# FPGA_PWR_CONFIG.net
KiCad netlist of a schematic drawn in Altium Designer
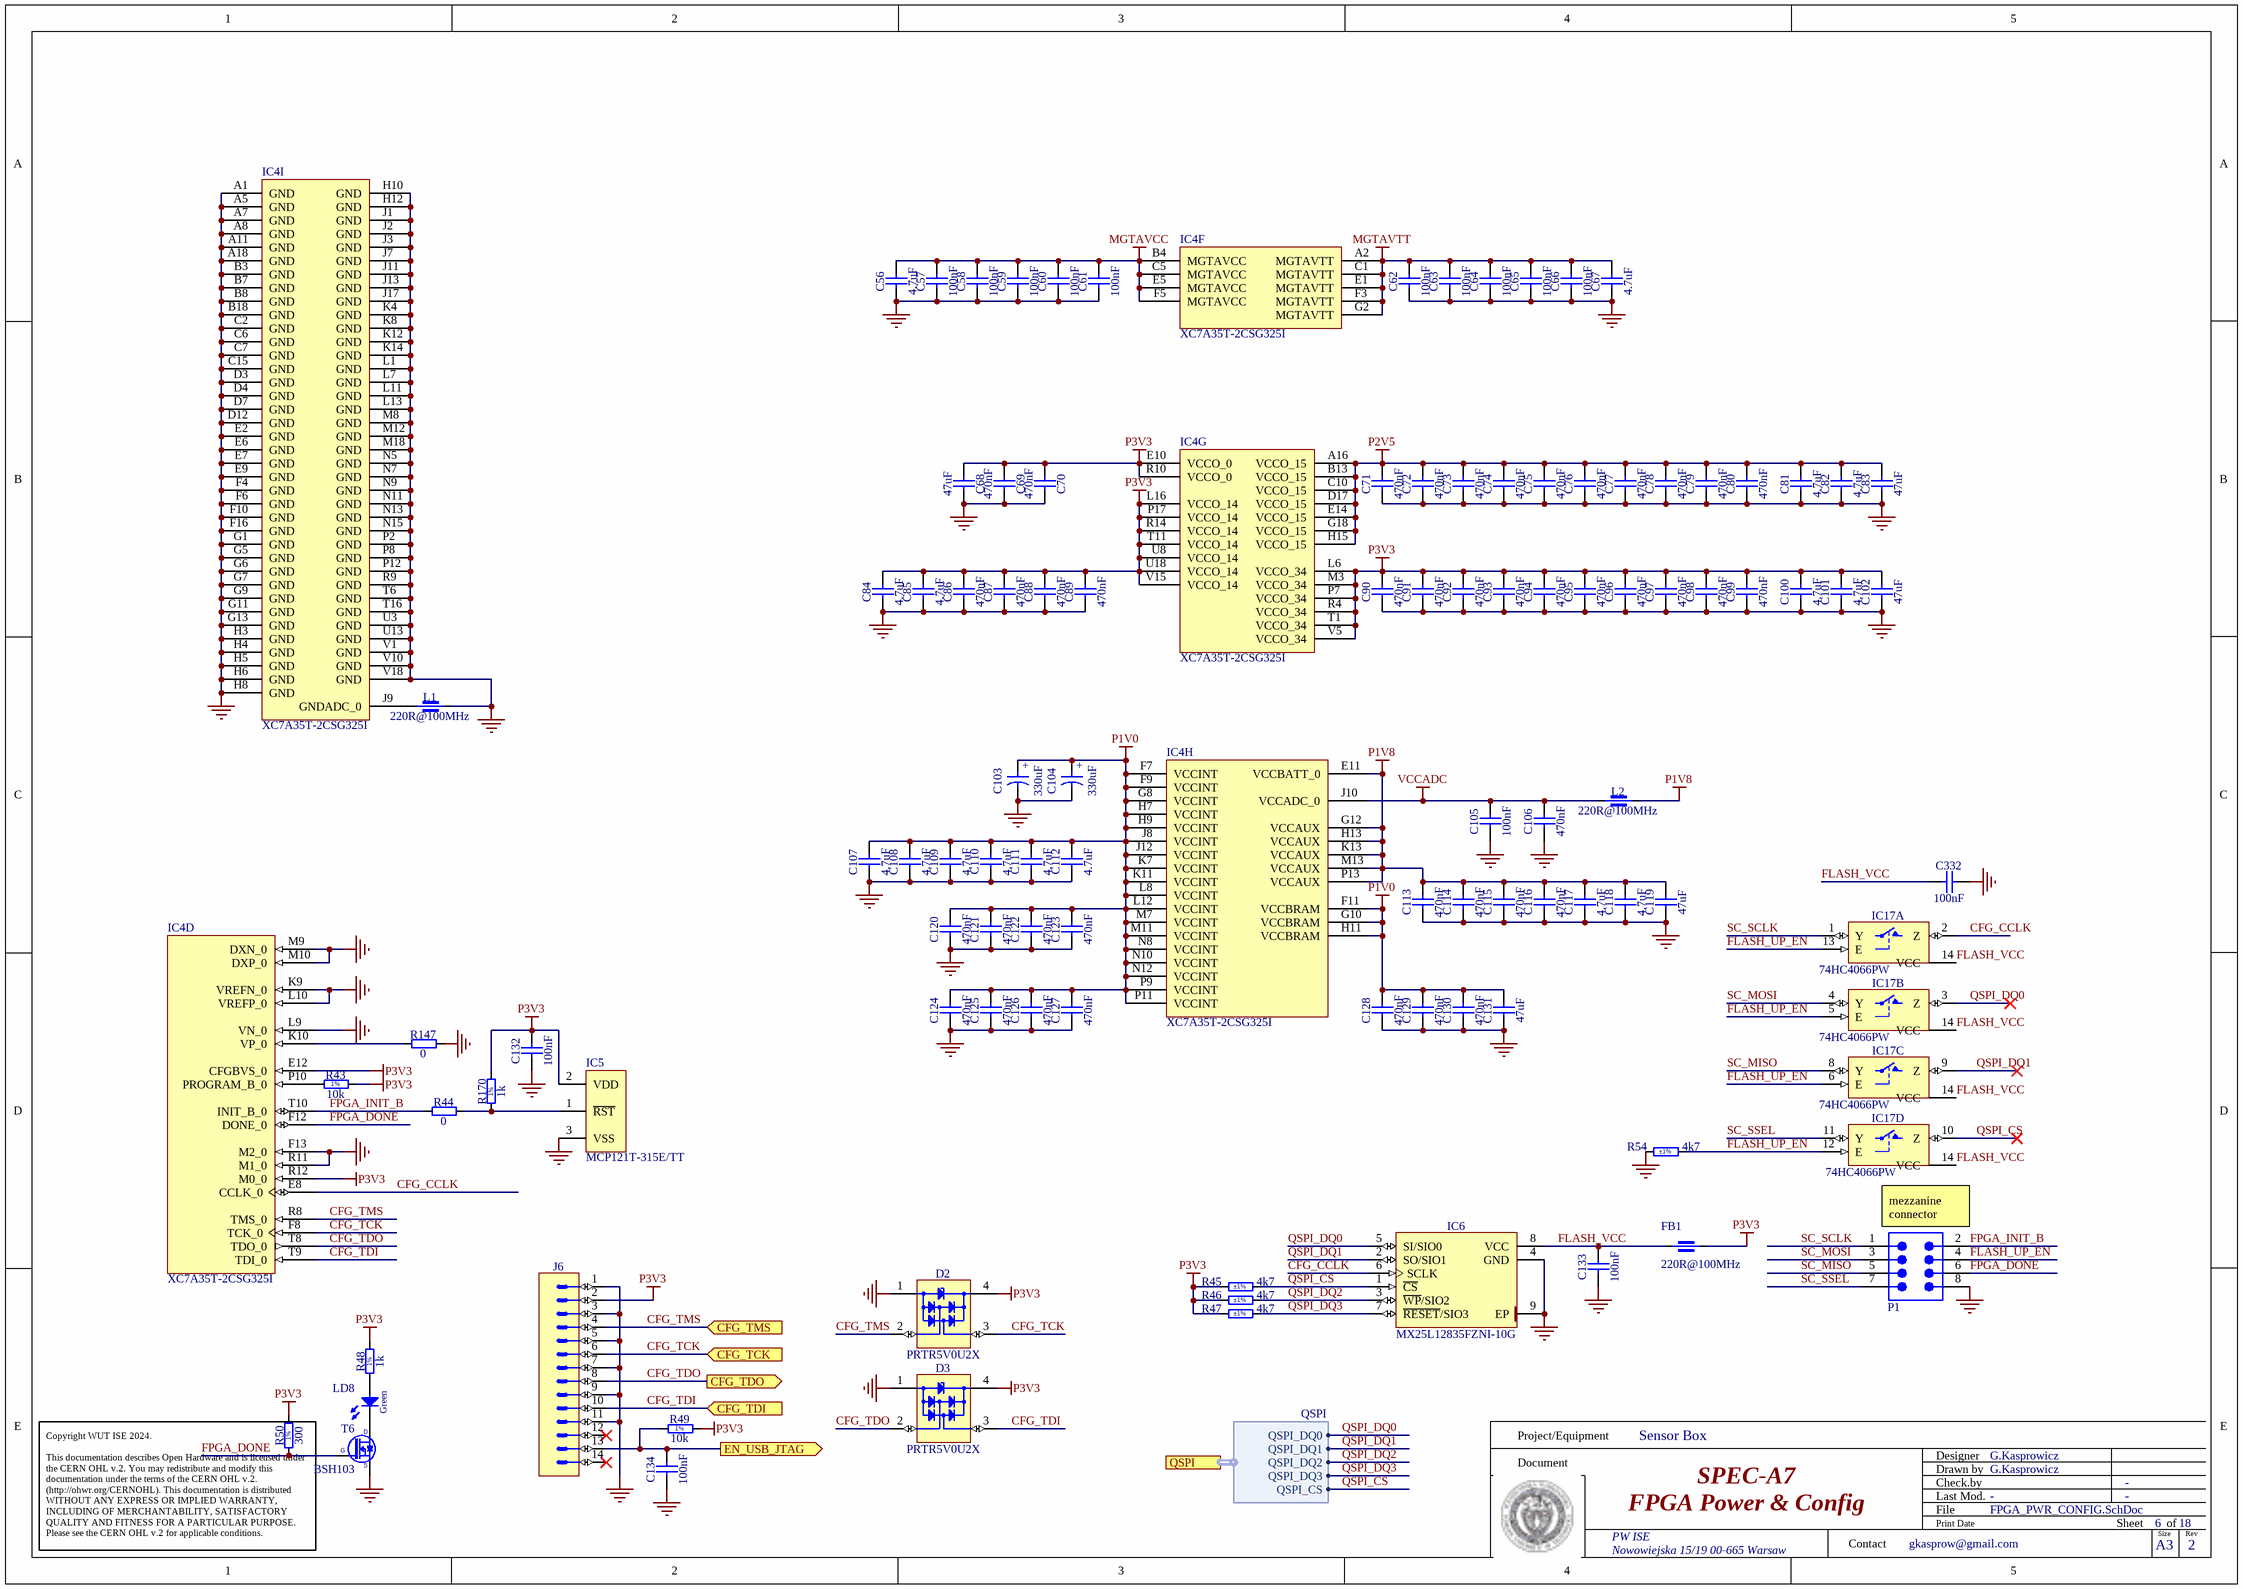
[diagram p0: FPGA_PWR_CONFIG.SchDoc]

(export (version "E")
  (design (tool "Eeschema 10.0.6"))
  (components
    (comp (ref "C56")
      (value "4.7uF")
      (footprint "CAPC1005X55N")
      (description "Non-polarised capacitor")
      (fields
        (field (name "PART NUMBER") "CC0402_4.7UF_6.3V_20%_X5R")
        (field (name "VOLTAGE") "6.3V")
        (field (name "AUTHOR") "CERN DEM JLC")
      )
      (libsource (lib "Capacitors") (part "Capacitor - non polarized"))
    )
    (comp (ref "C57")
      (value "100nF")
      (footprint "CAPC0603X33N")
      (description "Non-polarised capacitor")
      (fields
        (field (name "PART NUMBER") "CC0201_100NF_6.3V_10%_X5R")
        (field (name "VOLTAGE") "6.3V")
        (field (name "AUTHOR") "CERN DEM JLC")
      )
      (libsource (lib "Capacitors") (part "Capacitor - non polarized"))
    )
    (comp (ref "C58")
      (value "100nF")
      (footprint "CAPC0603X33N")
      (description "Non-polarised capacitor")
      (fields
        (field (name "PART NUMBER") "CC0201_100NF_6.3V_10%_X5R")
        (field (name "VOLTAGE") "6.3V")
        (field (name "AUTHOR") "CERN DEM JLC")
      )
      (libsource (lib "Capacitors") (part "Capacitor - non polarized"))
    )
    (comp (ref "C59")
      (value "100nF")
      (footprint "CAPC0603X33N")
      (description "Non-polarised capacitor")
      (fields
        (field (name "PART NUMBER") "CC0201_100NF_6.3V_10%_X5R")
        (field (name "VOLTAGE") "6.3V")
        (field (name "AUTHOR") "CERN DEM JLC")
      )
      (libsource (lib "Capacitors") (part "Capacitor - non polarized"))
    )
    (comp (ref "C60")
      (value "100nF")
      (footprint "CAPC0603X33N")
      (description "Non-polarised capacitor")
      (fields
        (field (name "PART NUMBER") "CC0201_100NF_6.3V_10%_X5R")
        (field (name "VOLTAGE") "6.3V")
        (field (name "AUTHOR") "CERN DEM JLC")
      )
      (libsource (lib "Capacitors") (part "Capacitor - non polarized"))
    )
    (comp (ref "C61")
      (value "100nF")
      (footprint "CAPC0603X33N")
      (description "Non-polarised capacitor")
      (fields
        (field (name "PART NUMBER") "CC0201_100NF_6.3V_10%_X5R")
        (field (name "VOLTAGE") "6.3V")
        (field (name "AUTHOR") "CERN DEM JLC")
      )
      (libsource (lib "Capacitors") (part "Capacitor - non polarized"))
    )
    (comp (ref "C62")
      (value "100nF")
      (footprint "CAPC0603X33N")
      (description "Non-polarised capacitor")
      (fields
        (field (name "PART NUMBER") "CC0201_100NF_6.3V_10%_X5R")
        (field (name "VOLTAGE") "6.3V")
        (field (name "AUTHOR") "CERN DEM JLC")
      )
      (libsource (lib "Capacitors") (part "Capacitor - non polarized"))
    )
    (comp (ref "C63")
      (value "100nF")
      (footprint "CAPC0603X33N")
      (description "Non-polarised capacitor")
      (fields
        (field (name "PART NUMBER") "CC0201_100NF_6.3V_10%_X5R")
        (field (name "VOLTAGE") "6.3V")
        (field (name "AUTHOR") "CERN DEM JLC")
      )
      (libsource (lib "Capacitors") (part "Capacitor - non polarized"))
    )
    (comp (ref "C64")
      (value "100nF")
      (footprint "CAPC0603X33N")
      (description "Non-polarised capacitor")
      (fields
        (field (name "PART NUMBER") "CC0201_100NF_6.3V_10%_X5R")
        (field (name "VOLTAGE") "6.3V")
        (field (name "AUTHOR") "CERN DEM JLC")
      )
      (libsource (lib "Capacitors") (part "Capacitor - non polarized"))
    )
    (comp (ref "C65")
      (value "100nF")
      (footprint "CAPC0603X33N")
      (description "Non-polarised capacitor")
      (fields
        (field (name "PART NUMBER") "CC0201_100NF_6.3V_10%_X5R")
        (field (name "VOLTAGE") "6.3V")
        (field (name "AUTHOR") "CERN DEM JLC")
      )
      (libsource (lib "Capacitors") (part "Capacitor - non polarized"))
    )
    (comp (ref "C66")
      (value "100nF")
      (footprint "CAPC0603X33N")
      (description "Non-polarised capacitor")
      (fields
        (field (name "PART NUMBER") "CC0201_100NF_6.3V_10%_X5R")
        (field (name "VOLTAGE") "6.3V")
        (field (name "AUTHOR") "CERN DEM JLC")
      )
      (libsource (lib "Capacitors") (part "Capacitor - non polarized"))
    )
    (comp (ref "C67")
      (value "4.7uF")
      (footprint "CAPC1005X55N")
      (description "Non-polarised capacitor")
      (fields
        (field (name "PART NUMBER") "CC0402_4.7UF_6.3V_20%_X5R")
        (field (name "VOLTAGE") "6.3V")
        (field (name "AUTHOR") "CERN DEM JLC")
      )
      (libsource (lib "Capacitors") (part "Capacitor - non polarized"))
    )
    (comp (ref "C68")
      (value "47uF")
      (footprint "CAPC1608X100N")
      (description "Non-polarised capacitor")
      (fields
        (field (name "PART NUMBER") "CC0603_47UF_6.3V_20%_X5R")
        (field (name "VOLTAGE") "6.3V")
        (field (name "AUTHOR") "CERN DEM JLC")
      )
      (libsource (lib "Capacitors") (part "Capacitor - non polarized"))
    )
    (comp (ref "C69")
      (value "470nF")
      (footprint "CAPC0603X33N")
      (description "Non-polarised capacitor")
      (fields
        (field (name "PART NUMBER") "CC0201_470NF_4V_20%_X5R")
        (field (name "VOLTAGE") "4V")
        (field (name "AUTHOR") "CERN DEM JLC")
      )
      (libsource (lib "Capacitors") (part "Capacitor - non polarized"))
    )
    (comp (ref "C70")
      (value "470nF")
      (footprint "CAPC0603X33N")
      (description "Non-polarised capacitor")
      (fields
        (field (name "PART NUMBER") "CC0201_470NF_4V_20%_X5R")
        (field (name "VOLTAGE") "4V")
        (field (name "AUTHOR") "CERN DEM JLC")
      )
      (libsource (lib "Capacitors") (part "Capacitor - non polarized"))
    )
    (comp (ref "C71")
      (value "470nF")
      (footprint "CAPC0603X33N")
      (description "Non-polarised capacitor")
      (fields
        (field (name "PART NUMBER") "CC0201_470NF_4V_20%_X5R")
        (field (name "VOLTAGE") "4V")
        (field (name "AUTHOR") "CERN DEM JLC")
      )
      (libsource (lib "Capacitors") (part "Capacitor - non polarized"))
    )
    (comp (ref "C72")
      (value "470nF")
      (footprint "CAPC0603X33N")
      (description "Non-polarised capacitor")
      (fields
        (field (name "PART NUMBER") "CC0201_470NF_4V_20%_X5R")
        (field (name "VOLTAGE") "4V")
        (field (name "AUTHOR") "CERN DEM JLC")
      )
      (libsource (lib "Capacitors") (part "Capacitor - non polarized"))
    )
    (comp (ref "C73")
      (value "470nF")
      (footprint "CAPC0603X33N")
      (description "Non-polarised capacitor")
      (fields
        (field (name "PART NUMBER") "CC0201_470NF_4V_20%_X5R")
        (field (name "VOLTAGE") "4V")
        (field (name "AUTHOR") "CERN DEM JLC")
      )
      (libsource (lib "Capacitors") (part "Capacitor - non polarized"))
    )
    (comp (ref "C74")
      (value "470nF")
      (footprint "CAPC0603X33N")
      (description "Non-polarised capacitor")
      (fields
        (field (name "PART NUMBER") "CC0201_470NF_4V_20%_X5R")
        (field (name "VOLTAGE") "4V")
        (field (name "AUTHOR") "CERN DEM JLC")
      )
      (libsource (lib "Capacitors") (part "Capacitor - non polarized"))
    )
    (comp (ref "C75")
      (value "470nF")
      (footprint "CAPC0603X33N")
      (description "Non-polarised capacitor")
      (fields
        (field (name "PART NUMBER") "CC0201_470NF_4V_20%_X5R")
        (field (name "VOLTAGE") "4V")
        (field (name "AUTHOR") "CERN DEM JLC")
      )
      (libsource (lib "Capacitors") (part "Capacitor - non polarized"))
    )
    (comp (ref "C76")
      (value "470nF")
      (footprint "CAPC0603X33N")
      (description "Non-polarised capacitor")
      (fields
        (field (name "PART NUMBER") "CC0201_470NF_4V_20%_X5R")
        (field (name "VOLTAGE") "4V")
        (field (name "AUTHOR") "CERN DEM JLC")
      )
      (libsource (lib "Capacitors") (part "Capacitor - non polarized"))
    )
    (comp (ref "C77")
      (value "470nF")
      (footprint "CAPC0603X33N")
      (description "Non-polarised capacitor")
      (fields
        (field (name "PART NUMBER") "CC0201_470NF_4V_20%_X5R")
        (field (name "VOLTAGE") "4V")
        (field (name "AUTHOR") "CERN DEM JLC")
      )
      (libsource (lib "Capacitors") (part "Capacitor - non polarized"))
    )
    (comp (ref "C78")
      (value "470nF")
      (footprint "CAPC0603X33N")
      (description "Non-polarised capacitor")
      (fields
        (field (name "PART NUMBER") "CC0201_470NF_4V_20%_X5R")
        (field (name "VOLTAGE") "4V")
        (field (name "AUTHOR") "CERN DEM JLC")
      )
      (libsource (lib "Capacitors") (part "Capacitor - non polarized"))
    )
    (comp (ref "C79")
      (value "470nF")
      (footprint "CAPC0603X33N")
      (description "Non-polarised capacitor")
      (fields
        (field (name "PART NUMBER") "CC0201_470NF_4V_20%_X5R")
        (field (name "VOLTAGE") "4V")
        (field (name "AUTHOR") "CERN DEM JLC")
      )
      (libsource (lib "Capacitors") (part "Capacitor - non polarized"))
    )
    (comp (ref "C80")
      (value "470nF")
      (footprint "CAPC0603X33N")
      (description "Non-polarised capacitor")
      (fields
        (field (name "PART NUMBER") "CC0201_470NF_4V_20%_X5R")
        (field (name "VOLTAGE") "4V")
        (field (name "AUTHOR") "CERN DEM JLC")
      )
      (libsource (lib "Capacitors") (part "Capacitor - non polarized"))
    )
    (comp (ref "C81")
      (value "4.7uF")
      (footprint "CAPC1005X55N")
      (description "Non-polarised capacitor")
      (fields
        (field (name "PART NUMBER") "CC0402_4.7UF_6.3V_20%_X5R")
        (field (name "VOLTAGE") "6.3V")
        (field (name "AUTHOR") "CERN DEM JLC")
      )
      (libsource (lib "Capacitors") (part "Capacitor - non polarized"))
    )
    (comp (ref "C82")
      (value "4.7uF")
      (footprint "CAPC1005X55N")
      (description "Non-polarised capacitor")
      (fields
        (field (name "PART NUMBER") "CC0402_4.7UF_6.3V_20%_X5R")
        (field (name "VOLTAGE") "6.3V")
        (field (name "AUTHOR") "CERN DEM JLC")
      )
      (libsource (lib "Capacitors") (part "Capacitor - non polarized"))
    )
    (comp (ref "C83")
      (value "47uF")
      (footprint "CAPC1608X100N")
      (description "Non-polarised capacitor")
      (fields
        (field (name "PART NUMBER") "CC0603_47UF_6.3V_20%_X5R")
        (field (name "VOLTAGE") "6.3V")
        (field (name "AUTHOR") "CERN DEM JLC")
      )
      (libsource (lib "Capacitors") (part "Capacitor - non polarized"))
    )
    (comp (ref "C84")
      (value "4.7uF")
      (footprint "CAPC1005X55N")
      (description "Non-polarised capacitor")
      (fields
        (field (name "PART NUMBER") "CC0402_4.7UF_6.3V_20%_X5R")
        (field (name "VOLTAGE") "6.3V")
        (field (name "AUTHOR") "CERN DEM JLC")
      )
      (libsource (lib "Capacitors") (part "Capacitor - non polarized"))
    )
    (comp (ref "C85")
      (value "4.7uF")
      (footprint "CAPC1005X55N")
      (description "Non-polarised capacitor")
      (fields
        (field (name "PART NUMBER") "CC0402_4.7UF_6.3V_20%_X5R")
        (field (name "VOLTAGE") "6.3V")
        (field (name "AUTHOR") "CERN DEM JLC")
      )
      (libsource (lib "Capacitors") (part "Capacitor - non polarized"))
    )
    (comp (ref "C86")
      (value "470nF")
      (footprint "CAPC0603X33N")
      (description "Non-polarised capacitor")
      (fields
        (field (name "PART NUMBER") "CC0201_470NF_4V_20%_X5R")
        (field (name "VOLTAGE") "4V")
        (field (name "AUTHOR") "CERN DEM JLC")
      )
      (libsource (lib "Capacitors") (part "Capacitor - non polarized"))
    )
    (comp (ref "C87")
      (value "470nF")
      (footprint "CAPC0603X33N")
      (description "Non-polarised capacitor")
      (fields
        (field (name "PART NUMBER") "CC0201_470NF_4V_20%_X5R")
        (field (name "VOLTAGE") "4V")
        (field (name "AUTHOR") "CERN DEM JLC")
      )
      (libsource (lib "Capacitors") (part "Capacitor - non polarized"))
    )
    (comp (ref "C88")
      (value "470nF")
      (footprint "CAPC0603X33N")
      (description "Non-polarised capacitor")
      (fields
        (field (name "PART NUMBER") "CC0201_470NF_4V_20%_X5R")
        (field (name "VOLTAGE") "4V")
        (field (name "AUTHOR") "CERN DEM JLC")
      )
      (libsource (lib "Capacitors") (part "Capacitor - non polarized"))
    )
    (comp (ref "C89")
      (value "470nF")
      (footprint "CAPC0603X33N")
      (description "Non-polarised capacitor")
      (fields
        (field (name "PART NUMBER") "CC0201_470NF_4V_20%_X5R")
        (field (name "VOLTAGE") "4V")
        (field (name "AUTHOR") "CERN DEM JLC")
      )
      (libsource (lib "Capacitors") (part "Capacitor - non polarized"))
    )
    (comp (ref "C90")
      (value "470nF")
      (footprint "CAPC0603X33N")
      (description "Non-polarised capacitor")
      (fields
        (field (name "PART NUMBER") "CC0201_470NF_4V_20%_X5R")
        (field (name "VOLTAGE") "4V")
        (field (name "AUTHOR") "CERN DEM JLC")
      )
      (libsource (lib "Capacitors") (part "Capacitor - non polarized"))
    )
    (comp (ref "C91")
      (value "470nF")
      (footprint "CAPC0603X33N")
      (description "Non-polarised capacitor")
      (fields
        (field (name "PART NUMBER") "CC0201_470NF_4V_20%_X5R")
        (field (name "VOLTAGE") "4V")
        (field (name "AUTHOR") "CERN DEM JLC")
      )
      (libsource (lib "Capacitors") (part "Capacitor - non polarized"))
    )
    (comp (ref "C92")
      (value "470nF")
      (footprint "CAPC0603X33N")
      (description "Non-polarised capacitor")
      (fields
        (field (name "PART NUMBER") "CC0201_470NF_4V_20%_X5R")
        (field (name "VOLTAGE") "4V")
        (field (name "AUTHOR") "CERN DEM JLC")
      )
      (libsource (lib "Capacitors") (part "Capacitor - non polarized"))
    )
    (comp (ref "C93")
      (value "470nF")
      (footprint "CAPC0603X33N")
      (description "Non-polarised capacitor")
      (fields
        (field (name "PART NUMBER") "CC0201_470NF_4V_20%_X5R")
        (field (name "VOLTAGE") "4V")
        (field (name "AUTHOR") "CERN DEM JLC")
      )
      (libsource (lib "Capacitors") (part "Capacitor - non polarized"))
    )
    (comp (ref "C94")
      (value "470nF")
      (footprint "CAPC0603X33N")
      (description "Non-polarised capacitor")
      (fields
        (field (name "PART NUMBER") "CC0201_470NF_4V_20%_X5R")
        (field (name "VOLTAGE") "4V")
        (field (name "AUTHOR") "CERN DEM JLC")
      )
      (libsource (lib "Capacitors") (part "Capacitor - non polarized"))
    )
    (comp (ref "C95")
      (value "470nF")
      (footprint "CAPC0603X33N")
      (description "Non-polarised capacitor")
      (fields
        (field (name "PART NUMBER") "CC0201_470NF_4V_20%_X5R")
        (field (name "VOLTAGE") "4V")
        (field (name "AUTHOR") "CERN DEM JLC")
      )
      (libsource (lib "Capacitors") (part "Capacitor - non polarized"))
    )
    (comp (ref "C96")
      (value "470nF")
      (footprint "CAPC0603X33N")
      (description "Non-polarised capacitor")
      (fields
        (field (name "PART NUMBER") "CC0201_470NF_4V_20%_X5R")
        (field (name "VOLTAGE") "4V")
        (field (name "AUTHOR") "CERN DEM JLC")
      )
      (libsource (lib "Capacitors") (part "Capacitor - non polarized"))
    )
    (comp (ref "C97")
      (value "470nF")
      (footprint "CAPC0603X33N")
      (description "Non-polarised capacitor")
      (fields
        (field (name "PART NUMBER") "CC0201_470NF_4V_20%_X5R")
        (field (name "VOLTAGE") "4V")
        (field (name "AUTHOR") "CERN DEM JLC")
      )
      (libsource (lib "Capacitors") (part "Capacitor - non polarized"))
    )
    (comp (ref "C98")
      (value "470nF")
      (footprint "CAPC0603X33N")
      (description "Non-polarised capacitor")
      (fields
        (field (name "PART NUMBER") "CC0201_470NF_4V_20%_X5R")
        (field (name "VOLTAGE") "4V")
        (field (name "AUTHOR") "CERN DEM JLC")
      )
      (libsource (lib "Capacitors") (part "Capacitor - non polarized"))
    )
    (comp (ref "C99")
      (value "470nF")
      (footprint "CAPC0603X33N")
      (description "Non-polarised capacitor")
      (fields
        (field (name "PART NUMBER") "CC0201_470NF_4V_20%_X5R")
        (field (name "VOLTAGE") "4V")
        (field (name "AUTHOR") "CERN DEM JLC")
      )
      (libsource (lib "Capacitors") (part "Capacitor - non polarized"))
    )
    (comp (ref "C100")
      (value "4.7uF")
      (footprint "CAPC1005X55N")
      (description "Non-polarised capacitor")
      (fields
        (field (name "PART NUMBER") "CC0402_4.7UF_6.3V_20%_X5R")
        (field (name "VOLTAGE") "6.3V")
        (field (name "AUTHOR") "CERN DEM JLC")
      )
      (libsource (lib "Capacitors") (part "Capacitor - non polarized"))
    )
    (comp (ref "C101")
      (value "4.7uF")
      (footprint "CAPC1005X55N")
      (description "Non-polarised capacitor")
      (fields
        (field (name "PART NUMBER") "CC0402_4.7UF_6.3V_20%_X5R")
        (field (name "VOLTAGE") "6.3V")
        (field (name "AUTHOR") "CERN DEM JLC")
      )
      (libsource (lib "Capacitors") (part "Capacitor - non polarized"))
    )
    (comp (ref "C102")
      (value "47uF")
      (footprint "CAPC1608X100N")
      (description "Non-polarised capacitor")
      (fields
        (field (name "PART NUMBER") "CC0603_47UF_6.3V_20%_X5R")
        (field (name "VOLTAGE") "6.3V")
        (field (name "AUTHOR") "CERN DEM JLC")
      )
      (libsource (lib "Capacitors") (part "Capacitor - non polarized"))
    )
    (comp (ref "C103")
      (value "330uF")
      (footprint "CAPMP7343X190N")
      (description "Polarised capacitor")
      (fields
        (field (name "PART NUMBER") "CTE7343-19_330UF_2.5V_20%_LESR0025_KEMET_T520")
        (field (name "VOLTAGE") "2.5V")
        (field (name "AUTHOR") "CERN DEM MR")
      )
      (libsource (lib "Capacitors") (part "Capacitor - polarized"))
    )
    (comp (ref "C104")
      (value "330uF")
      (footprint "CAPMP7343X190N")
      (description "Polarised capacitor")
      (fields
        (field (name "PART NUMBER") "CTE7343-19_330UF_2.5V_20%_LESR0025_KEMET_T520")
        (field (name "VOLTAGE") "2.5V")
        (field (name "AUTHOR") "CERN DEM MR")
      )
      (libsource (lib "Capacitors") (part "Capacitor - polarized"))
    )
    (comp (ref "C105")
      (value "100nF")
      (footprint "CAPC0603X33N")
      (description "Non-polarised capacitor")
      (fields
        (field (name "PART NUMBER") "CC0201_100NF_6.3V_10%_X5R")
        (field (name "VOLTAGE") "6.3V")
        (field (name "AUTHOR") "CERN DEM JLC")
      )
      (libsource (lib "Capacitors") (part "Capacitor - non polarized"))
    )
    (comp (ref "C106")
      (value "470nF")
      (footprint "CAPC0603X33N")
      (description "Non-polarised capacitor")
      (fields
        (field (name "PART NUMBER") "CC0201_470NF_4V_20%_X5R")
        (field (name "VOLTAGE") "4V")
        (field (name "AUTHOR") "CERN DEM JLC")
      )
      (libsource (lib "Capacitors") (part "Capacitor - non polarized"))
    )
    (comp (ref "C107")
      (value "4.7uF")
      (footprint "CAPC1005X55N")
      (description "Non-polarised capacitor")
      (fields
        (field (name "PART NUMBER") "CC0402_4.7UF_6.3V_20%_X5R")
        (field (name "VOLTAGE") "6.3V")
        (field (name "AUTHOR") "CERN DEM JLC")
      )
      (libsource (lib "Capacitors") (part "Capacitor - non polarized"))
    )
    (comp (ref "C108")
      (value "4.7uF")
      (footprint "CAPC1005X55N")
      (description "Non-polarised capacitor")
      (fields
        (field (name "PART NUMBER") "CC0402_4.7UF_6.3V_20%_X5R")
        (field (name "VOLTAGE") "6.3V")
        (field (name "AUTHOR") "CERN DEM JLC")
      )
      (libsource (lib "Capacitors") (part "Capacitor - non polarized"))
    )
    (comp (ref "C109")
      (value "4.7uF")
      (footprint "CAPC1005X55N")
      (description "Non-polarised capacitor")
      (fields
        (field (name "PART NUMBER") "CC0402_4.7UF_6.3V_20%_X5R")
        (field (name "VOLTAGE") "6.3V")
        (field (name "AUTHOR") "CERN DEM JLC")
      )
      (libsource (lib "Capacitors") (part "Capacitor - non polarized"))
    )
    (comp (ref "C110")
      (value "4.7uF")
      (footprint "CAPC1005X55N")
      (description "Non-polarised capacitor")
      (fields
        (field (name "PART NUMBER") "CC0402_4.7UF_6.3V_20%_X5R")
        (field (name "VOLTAGE") "6.3V")
        (field (name "AUTHOR") "CERN DEM JLC")
      )
      (libsource (lib "Capacitors") (part "Capacitor - non polarized"))
    )
    (comp (ref "C111")
      (value "4.7uF")
      (footprint "CAPC1005X55N")
      (description "Non-polarised capacitor")
      (fields
        (field (name "PART NUMBER") "CC0402_4.7UF_6.3V_20%_X5R")
        (field (name "VOLTAGE") "6.3V")
        (field (name "AUTHOR") "CERN DEM JLC")
      )
      (libsource (lib "Capacitors") (part "Capacitor - non polarized"))
    )
    (comp (ref "C112")
      (value "4.7uF")
      (footprint "CAPC1005X55N")
      (description "Non-polarised capacitor")
      (fields
        (field (name "PART NUMBER") "CC0402_4.7UF_6.3V_20%_X5R")
        (field (name "VOLTAGE") "6.3V")
        (field (name "AUTHOR") "CERN DEM JLC")
      )
      (libsource (lib "Capacitors") (part "Capacitor - non polarized"))
    )
    (comp (ref "C113")
      (value "470nF")
      (footprint "CAPC0603X33N")
      (description "Non-polarised capacitor")
      (fields
        (field (name "PART NUMBER") "CC0201_470NF_4V_20%_X5R")
        (field (name "VOLTAGE") "4V")
        (field (name "AUTHOR") "CERN DEM JLC")
      )
      (libsource (lib "Capacitors") (part "Capacitor - non polarized"))
    )
    (comp (ref "C114")
      (value "470nF")
      (footprint "CAPC0603X33N")
      (description "Non-polarised capacitor")
      (fields
        (field (name "PART NUMBER") "CC0201_470NF_4V_20%_X5R")
        (field (name "VOLTAGE") "4V")
        (field (name "AUTHOR") "CERN DEM JLC")
      )
      (libsource (lib "Capacitors") (part "Capacitor - non polarized"))
    )
    (comp (ref "C115")
      (value "470nF")
      (footprint "CAPC0603X33N")
      (description "Non-polarised capacitor")
      (fields
        (field (name "PART NUMBER") "CC0201_470NF_4V_20%_X5R")
        (field (name "VOLTAGE") "4V")
        (field (name "AUTHOR") "CERN DEM JLC")
      )
      (libsource (lib "Capacitors") (part "Capacitor - non polarized"))
    )
    (comp (ref "C116")
      (value "470nF")
      (footprint "CAPC0603X33N")
      (description "Non-polarised capacitor")
      (fields
        (field (name "PART NUMBER") "CC0201_470NF_4V_20%_X5R")
        (field (name "VOLTAGE") "4V")
        (field (name "AUTHOR") "CERN DEM JLC")
      )
      (libsource (lib "Capacitors") (part "Capacitor - non polarized"))
    )
    (comp (ref "C117")
      (value "4.7uF")
      (footprint "CAPC1005X55N")
      (description "Non-polarised capacitor")
      (fields
        (field (name "PART NUMBER") "CC0402_4.7UF_6.3V_20%_X5R")
        (field (name "VOLTAGE") "6.3V")
        (field (name "AUTHOR") "CERN DEM JLC")
      )
      (libsource (lib "Capacitors") (part "Capacitor - non polarized"))
    )
    (comp (ref "C118")
      (value "4.7uF")
      (footprint "CAPC1005X55N")
      (description "Non-polarised capacitor")
      (fields
        (field (name "PART NUMBER") "CC0402_4.7UF_6.3V_20%_X5R")
        (field (name "VOLTAGE") "6.3V")
        (field (name "AUTHOR") "CERN DEM JLC")
      )
      (libsource (lib "Capacitors") (part "Capacitor - non polarized"))
    )
    (comp (ref "C119")
      (value "47uF")
      (footprint "CAPC1608X100N")
      (description "Non-polarised capacitor")
      (fields
        (field (name "PART NUMBER") "CC0603_47UF_6.3V_20%_X5R")
        (field (name "VOLTAGE") "6.3V")
        (field (name "AUTHOR") "CERN DEM JLC")
      )
      (libsource (lib "Capacitors") (part "Capacitor - non polarized"))
    )
    (comp (ref "C120")
      (value "470nF")
      (footprint "CAPC0603X33N")
      (description "Non-polarised capacitor")
      (fields
        (field (name "PART NUMBER") "CC0201_470NF_4V_20%_X5R")
        (field (name "VOLTAGE") "4V")
        (field (name "AUTHOR") "CERN DEM JLC")
      )
      (libsource (lib "Capacitors") (part "Capacitor - non polarized"))
    )
    (comp (ref "C121")
      (value "470nF")
      (footprint "CAPC0603X33N")
      (description "Non-polarised capacitor")
      (fields
        (field (name "PART NUMBER") "CC0201_470NF_4V_20%_X5R")
        (field (name "VOLTAGE") "4V")
        (field (name "AUTHOR") "CERN DEM JLC")
      )
      (libsource (lib "Capacitors") (part "Capacitor - non polarized"))
    )
    (comp (ref "C122")
      (value "470nF")
      (footprint "CAPC0603X33N")
      (description "Non-polarised capacitor")
      (fields
        (field (name "PART NUMBER") "CC0201_470NF_4V_20%_X5R")
        (field (name "VOLTAGE") "4V")
        (field (name "AUTHOR") "CERN DEM JLC")
      )
      (libsource (lib "Capacitors") (part "Capacitor - non polarized"))
    )
    (comp (ref "C123")
      (value "470nF")
      (footprint "CAPC0603X33N")
      (description "Non-polarised capacitor")
      (fields
        (field (name "PART NUMBER") "CC0201_470NF_4V_20%_X5R")
        (field (name "VOLTAGE") "4V")
        (field (name "AUTHOR") "CERN DEM JLC")
      )
      (libsource (lib "Capacitors") (part "Capacitor - non polarized"))
    )
    (comp (ref "C124")
      (value "470nF")
      (footprint "CAPC0603X33N")
      (description "Non-polarised capacitor")
      (fields
        (field (name "PART NUMBER") "CC0201_470NF_4V_20%_X5R")
        (field (name "VOLTAGE") "4V")
        (field (name "AUTHOR") "CERN DEM JLC")
      )
      (libsource (lib "Capacitors") (part "Capacitor - non polarized"))
    )
    (comp (ref "C125")
      (value "470nF")
      (footprint "CAPC0603X33N")
      (description "Non-polarised capacitor")
      (fields
        (field (name "PART NUMBER") "CC0201_470NF_4V_20%_X5R")
        (field (name "VOLTAGE") "4V")
        (field (name "AUTHOR") "CERN DEM JLC")
      )
      (libsource (lib "Capacitors") (part "Capacitor - non polarized"))
    )
    (comp (ref "C126")
      (value "470nF")
      (footprint "CAPC0603X33N")
      (description "Non-polarised capacitor")
      (fields
        (field (name "PART NUMBER") "CC0201_470NF_4V_20%_X5R")
        (field (name "VOLTAGE") "4V")
        (field (name "AUTHOR") "CERN DEM JLC")
      )
      (libsource (lib "Capacitors") (part "Capacitor - non polarized"))
    )
    (comp (ref "C127")
      (value "470nF")
      (footprint "CAPC0603X33N")
      (description "Non-polarised capacitor")
      (fields
        (field (name "PART NUMBER") "CC0201_470NF_4V_20%_X5R")
        (field (name "VOLTAGE") "4V")
        (field (name "AUTHOR") "CERN DEM JLC")
      )
      (libsource (lib "Capacitors") (part "Capacitor - non polarized"))
    )
    (comp (ref "C128")
      (value "470nF")
      (footprint "CAPC0603X33N")
      (description "Non-polarised capacitor")
      (fields
        (field (name "PART NUMBER") "CC0201_470NF_4V_20%_X5R")
        (field (name "VOLTAGE") "4V")
        (field (name "AUTHOR") "CERN DEM JLC")
      )
      (libsource (lib "Capacitors") (part "Capacitor - non polarized"))
    )
    (comp (ref "C129")
      (value "470nF")
      (footprint "CAPC0603X33N")
      (description "Non-polarised capacitor")
      (fields
        (field (name "PART NUMBER") "CC0201_470NF_4V_20%_X5R")
        (field (name "VOLTAGE") "4V")
        (field (name "AUTHOR") "CERN DEM JLC")
      )
      (libsource (lib "Capacitors") (part "Capacitor - non polarized"))
    )
    (comp (ref "C130")
      (value "470nF")
      (footprint "CAPC0603X33N")
      (description "Non-polarised capacitor")
      (fields
        (field (name "PART NUMBER") "CC0201_470NF_4V_20%_X5R")
        (field (name "VOLTAGE") "4V")
        (field (name "AUTHOR") "CERN DEM JLC")
      )
      (libsource (lib "Capacitors") (part "Capacitor - non polarized"))
    )
    (comp (ref "C131")
      (value "47uF")
      (footprint "CAPC1608X100N")
      (description "Non-polarised capacitor")
      (fields
        (field (name "PART NUMBER") "CC0603_47UF_6.3V_20%_X5R")
        (field (name "VOLTAGE") "6.3V")
        (field (name "AUTHOR") "CERN DEM JLC")
      )
      (libsource (lib "Capacitors") (part "Capacitor - non polarized"))
    )
    (comp (ref "C132")
      (value "100nF")
      (footprint "CAPC0603X33N")
      (description "Non-polarised capacitor")
      (fields
        (field (name "PART NUMBER") "CC0201_100NF_6.3V_10%_X5R")
        (field (name "VOLTAGE") "6.3V")
        (field (name "AUTHOR") "CERN DEM JLC")
      )
      (libsource (lib "Capacitors") (part "Capacitor - non polarized"))
    )
    (comp (ref "C133")
      (value "100nF")
      (footprint "CAPC0603X33N")
      (description "Non-polarised capacitor")
      (fields
        (field (name "PART NUMBER") "CC0201_100NF_6.3V_10%_X5R")
        (field (name "VOLTAGE") "6.3V")
        (field (name "AUTHOR") "CERN DEM JLC")
      )
      (libsource (lib "Capacitors") (part "Capacitor - non polarized"))
    )
    (comp (ref "C134")
      (value "100nF")
      (footprint "CAPC0603X33N")
      (description "Non-polarised capacitor")
      (fields
        (field (name "PART NUMBER") "CC0201_100NF_6.3V_10%_X5R")
        (field (name "VOLTAGE") "6.3V")
        (field (name "AUTHOR") "CERN DEM JLC")
      )
      (libsource (lib "Capacitors") (part "Capacitor - non polarized"))
    )
    (comp (ref "C332")
      (value "100nF")
      (footprint "CAPC0603X33N")
      (description "Non-polarised capacitor")
      (fields
        (field (name "PART NUMBER") "CC0201_100NF_6.3V_10%_X5R")
        (field (name "VOLTAGE") "6.3V")
        (field (name "AUTHOR") "CERN DEM JLC")
      )
      (libsource (lib "Capacitors") (part "Capacitor - non polarized"))
    )
    (comp (ref "D2")
      (value "PRTR5V0U2X")
      (footprint "SOT190P230X110-4N")
      (description "Ultra Low Capacitance Double Rail-to-Rail ESD Protection Diode")
      (fields
        (field (name "VOLTAGE") "5.5V")
        (field (name "MANUFACTURER") "NXP SEMICONDUCTORS")
        (field (name "AUTHOR") "CERN DEM JLC")
      )
      (libsource (lib "ICs And Semiconductors") (part "PRTR5V0U2X"))
    )
    (comp (ref "D3")
      (value "PRTR5V0U2X")
      (footprint "SOT190P230X110-4N")
      (description "Ultra Low Capacitance Double Rail-to-Rail ESD Protection Diode")
      (fields
        (field (name "VOLTAGE") "5.5V")
        (field (name "MANUFACTURER") "NXP SEMICONDUCTORS")
        (field (name "AUTHOR") "CERN DEM JLC")
      )
      (libsource (lib "ICs And Semiconductors") (part "PRTR5V0U2X"))
    )
    (comp (ref "FB1")
      (value "220R@100MHz")
      (footprint "INDC1608X95N")
      (fields
        (field (name "TOLERANCE") "±25%")
        (field (name "PART NUMBER") "IND0603_MURATA_BLM18SG221TN1")
        (field (name "POWER") "2.5A")
        (field (name "AUTHOR") "CERN DEM MR")
      )
      (libsource (lib "") (part "Ferrite Bead_1"))
    )
    (comp (ref "IC4")
      (value "XC7A35T-2CSG325I")
      (footprint "CSG325")
      (description "Artix-7 FPGA, 150 User I/Os, 4 GTP, 324-Ball BGA, Speed Grade 2, Industrial Grade, Pb-Free")
      (fields (field (name "MANUFACTURER") "Xilinx"))
      (libsource (lib "Altium Content Vault") (part "XLNX-XC7A35T-CSG325"))
    )
    (comp (ref "IC5")
      (value "MCP121T-315E/TT")
      (footprint "SOT-23-TT3_L")
      (description "Micropower Voltage Supervisors, 3-Pin SOT-23, Extended Temperature, Tape and Reel")
      (libsource (lib "Altium Content Vault") (part "PM-SCCT-MCP121-3"))
    )
    (comp (ref "IC6")
      (value "MX25L12835FZNI-10G")
      (footprint "SON127P600X500X80-9N-R350X410")
      (description "128Mb, 3V, Serial Multi I/O Flash Memory")
      (fields (field (name "MANUFACTURER") "MACRONIX") (field (name "AUTHOR") "CERN DEM HF"))
      (libsource (lib "ICs And Semiconductors") (part "MX25L12835FZNI-10G"))
    )
    (comp (ref "IC17")
      (value "74HC4066PW")
      (footprint "SOP65P640X110-14N")
      (fields (field (name "MANUFACTURER") "NXP SEMICONDUCTORS") (field (name "AUTHOR") "CERN DEM JLC"))
      (libsource (lib "ICs And Semiconductors") (part "4066"))
    )
    (comp (ref "J6")
      (value "Milli-Grid™")
      (footprint "MOLEX_87832-1420")
      (description "Connector 14 Male")
      (fields
        (field (name "PART NUMBER") "MOLEX_87832-1420")
        (field (name "MANUFACTURER") "MOLEX")
        (field (name "AUTHOR") "CERN DEM JLC")
      )
      (libsource (lib "Connectors") (part "Connector 14 Male"))
    )
    (comp (ref "L1")
      (value "220R@100MHz")
      (footprint "INDC1005X55N")
      (fields
        (field (name "PART NUMBER") "IND0402_MURATA_BLM15HB221SN1")
        (field (name "POWER") "250mA")
        (field (name "TOLERANCE") "±25%")
        (field (name "AUTHOR") "CERN DEM JLC")
      )
      (libsource (lib "Inductors & Transformers") (part "Ferrite Bead"))
    )
    (comp (ref "L2")
      (value "220R@100MHz")
      (footprint "INDC1005X55N")
      (fields
        (field (name "PART NUMBER") "IND0402_MURATA_BLM15HB221SN1")
        (field (name "POWER") "250mA")
        (field (name "TOLERANCE") "±25%")
        (field (name "AUTHOR") "CERN DEM JLC")
      )
      (libsource (lib "Inductors & Transformers") (part "Ferrite Bead"))
    )
    (comp (ref "LD8")
      (value "Green")
      (footprint "LED_KINGBRIGHT_KPH-1608CGCK")
      (description "LED Green 1C 2A")
      (fields
        (field (name "MANUFACTURER PART NUMBER") "KPH-1608CGCK")
        (field (name "PART NUMBER") "LED_KINGBRIGHT_KPH-1608CGCK")
        (field (name "AUTHOR") "CERN DEM JLC")
      )
      (libsource (lib "ICs And Semiconductors") (part "LED Green 1C 2A"))
    )
    (comp (ref "P1")
      (value "61300821121")
      (footprint "61300821121")
      (description "WR-PHD Pin Header, THT, Vertical, pitch 2.54mm, 2 Row, 8P")
      (fields (field (name "MANUFACTURER") "Wurth Elektronik"))
      (libsource (lib "Altium_WR-PHD (rev24a)") (part "61300821121"))
    )
    (comp (ref "R43")
      (value "10k")
      (footprint "RESC1005X40N")
      (description "Resistor - 1%")
      (fields
        (field (name "PART NUMBER") "R0402_10K_1%_0.0625W_100PPM")
        (field (name "POWER") "0.0625W")
        (field (name "AUTHOR") "CERN DEM JLC")
      )
      (libsource (lib "Resistors") (part "Resistor - 1%"))
    )
    (comp (ref "R44")
      (value "0")
      (footprint "RESC1005X40N")
      (description "Resistor")
      (fields
        (field (name "PART NUMBER") "R0402_0R_JUMPER")
        (field (name "MANUFACTURER") "GENERIC")
        (field (name "AUTHOR") "CERN DEM JLC")
      )
      (libsource (lib "Resistors") (part "Resistor"))
    )
    (comp (ref "R45")
      (value "4k7")
      (footprint "RESC1005X40N")
      (description "Resistor - 1%")
      (fields
        (field (name "TOLERANCE") "±1%")
        (field (name "PART NUMBER") "R0402_4K7_1%_0.0625W_100PPM")
        (field (name "POWER") "0.0625W")
        (field (name "AUTHOR") "CERN DEM JLC")
      )
      (libsource (lib "Resistors") (part "Resistor - 1%"))
    )
    (comp (ref "R46")
      (value "4k7")
      (footprint "RESC1005X40N")
      (description "Resistor - 1%")
      (fields
        (field (name "TOLERANCE") "±1%")
        (field (name "PART NUMBER") "R0402_4K7_1%_0.0625W_100PPM")
        (field (name "POWER") "0.0625W")
        (field (name "AUTHOR") "CERN DEM JLC")
      )
      (libsource (lib "Resistors") (part "Resistor - 1%"))
    )
    (comp (ref "R47")
      (value "4k7")
      (footprint "RESC1005X40N")
      (description "Resistor - 1%")
      (fields
        (field (name "TOLERANCE") "±1%")
        (field (name "PART NUMBER") "R0402_4K7_1%_0.0625W_100PPM")
        (field (name "POWER") "0.0625W")
        (field (name "AUTHOR") "CERN DEM JLC")
      )
      (libsource (lib "Resistors") (part "Resistor - 1%"))
    )
    (comp (ref "R48")
      (value "1k")
      (footprint "RESC1005X40N")
      (description "Resistor - 1%")
      (fields
        (field (name "PART NUMBER") "R0402_1K_1%_0.0625W_100PPM")
        (field (name "POWER") "0.0625W")
        (field (name "AUTHOR") "CERN DEM JLC")
      )
      (libsource (lib "Resistors") (part "Resistor - 1%"))
    )
    (comp (ref "R49")
      (value "10k")
      (footprint "RESC1005X40N")
      (description "Resistor - 1%")
      (fields
        (field (name "PART NUMBER") "R0402_10K_1%_0.0625W_100PPM")
        (field (name "POWER") "0.0625W")
        (field (name "AUTHOR") "CERN DEM JLC")
      )
      (libsource (lib "Resistors") (part "Resistor - 1%"))
    )
    (comp (ref "R50")
      (value "300")
      (footprint "RESC1005X40N")
      (description "Resistor - 1%")
      (fields
        (field (name "PART NUMBER") "R0402_300R_1%_0.0625W_100PPM")
        (field (name "POWER") "0.0625W")
        (field (name "AUTHOR") "CERN DEM JLC")
      )
      (libsource (lib "Resistors") (part "Resistor - 1%"))
    )
    (comp (ref "R54")
      (value "4k7")
      (footprint "RESC1005X40N")
      (description "Resistor - 1%")
      (fields
        (field (name "TOLERANCE") "±1%")
        (field (name "PART NUMBER") "R0402_4K7_1%_0.0625W_100PPM")
        (field (name "POWER") "0.0625W")
        (field (name "AUTHOR") "CERN DEM JLC")
      )
      (libsource (lib "Resistors") (part "Resistor - 1%"))
    )
    (comp (ref "R147")
      (value "0")
      (footprint "RESC1005X40N")
      (description "Resistor")
      (fields
        (field (name "PART NUMBER") "R0402_0R_JUMPER")
        (field (name "MANUFACTURER") "GENERIC")
        (field (name "AUTHOR") "CERN DEM JLC")
      )
      (libsource (lib "Resistors") (part "Resistor"))
    )
    (comp (ref "R170")
      (value "1k")
      (footprint "RESC1005X40N")
      (description "Resistor - 1%")
      (fields
        (field (name "PART NUMBER") "R0402_1K_1%_0.0625W_100PPM")
        (field (name "POWER") "0.0625W")
        (field (name "AUTHOR") "CERN DEM JLC")
      )
      (libsource (lib "Resistors") (part "Resistor - 1%"))
    )
    (comp (ref "T6")
      (value "BSH103")
      (footprint "SOT95P230X110-3N")
      (description "N-CHANNEL MOSFET WITH DIODE")
      (fields (field (name "MANUFACTURER") "NEXPERIA") (field (name "AUTHOR") "CERN DEM JLC"))
      (libsource (lib "ICs And Semiconductors") (part "N-MOSFET-D 1G 2S 3D"))
    )
  )
  (nets
    (net (code "2") (name "/CFG_CCLK") (class "Default")
      (node (ref "IC17") (pin "2") (pinfunction "Z_2") (pintype "bidirectional"))
      (node (ref "IC4") (pin "E8") (pinfunction "CCLK_0_E8") (pintype "bidirectional"))
      (node (ref "IC6") (pin "6") (pinfunction "SCLK_6") (pintype "input"))
    )
    (net (code "3") (name "/CFG_TCK") (class "Default")
      (node (ref "D2") (pin "3") (pinfunction "I/O2_3") (pintype "bidirectional"))
      (node (ref "IC4") (pin "F8") (pinfunction "TCK_0_F8") (pintype "input"))
      (node (ref "J6") (pin "6") (pinfunction "6_6") (pintype "bidirectional"))
    )
    (net (code "4") (name "/CFG_TDI") (class "Default")
      (node (ref "D3") (pin "3") (pinfunction "I/O2_3") (pintype "bidirectional"))
      (node (ref "IC4") (pin "T9") (pinfunction "TDI_0_T9") (pintype "input"))
      (node (ref "J6") (pin "10") (pinfunction "10_10") (pintype "bidirectional"))
    )
    (net (code "5") (name "/CFG_TDO") (class "Default")
      (node (ref "D3") (pin "2") (pinfunction "I/O1_2") (pintype "bidirectional"))
      (node (ref "IC4") (pin "T8") (pinfunction "TDO_0_T8") (pintype "output"))
      (node (ref "J6") (pin "8") (pinfunction "8_8") (pintype "bidirectional"))
    )
    (net (code "6") (name "/CFG_TMS") (class "Default")
      (node (ref "D2") (pin "2") (pinfunction "I/O1_2") (pintype "bidirectional"))
      (node (ref "IC4") (pin "R8") (pinfunction "TMS_0_R8") (pintype "input"))
      (node (ref "J6") (pin "4") (pinfunction "4_4") (pintype "bidirectional"))
    )
    (net (code "7") (name "/EN_USB_JTAG") (class "Default")
      (node (ref "C134") (pin "2") (pinfunction "2_2") (pintype "passive"))
      (node (ref "J6") (pin "13") (pinfunction "13_13") (pintype "bidirectional"))
      (node (ref "R49") (pin "1") (pinfunction "1_1") (pintype "passive"))
    )
    (net (code "8") (name "/FLASH_UP_EN") (class "Default")
      (node (ref "IC17") (pin "12") (pinfunction "E_12") (pintype "input"))
      (node (ref "IC17") (pin "13") (pinfunction "E_13") (pintype "input"))
      (node (ref "IC17") (pin "5") (pinfunction "E_5") (pintype "input"))
      (node (ref "IC17") (pin "6") (pinfunction "E_6") (pintype "input"))
      (node (ref "P1") (pin "4") (pinfunction "4_4") (pintype "passive"))
      (node (ref "R54") (pin "2") (pinfunction "2_2") (pintype "passive"))
    )
    (net (code "9") (name "/FLASH_VCC") (class "Default")
      (node (ref "C133") (pin "2") (pinfunction "2_2") (pintype "passive"))
      (node (ref "C332") (pin "1") (pinfunction "1_1") (pintype "passive"))
      (node (ref "FB1") (pin "2") (pinfunction "2_2") (pintype "passive"))
      (node (ref "IC17") (pin "14") (pinfunction "VCC_14") (pintype "power_in"))
      (node (ref "IC6") (pin "8") (pinfunction "VCC_8") (pintype "power_in"))
    )
    (net (code "10") (name "/FPGA_DONE") (class "Default")
      (node (ref "IC4") (pin "F12") (pinfunction "DONE_0_F12") (pintype "bidirectional"))
      (node (ref "P1") (pin "6") (pinfunction "6_6") (pintype "passive"))
      (node (ref "R50") (pin "1") (pinfunction "1_1") (pintype "passive"))
      (node (ref "T6") (pin "1") (pinfunction "G_1") (pintype "passive"))
    )
    (net (code "11") (name "/FPGA_INIT_B") (class "Default")
      (node (ref "IC4") (pin "T10") (pinfunction "INIT_B_0_T10") (pintype "bidirectional"))
      (node (ref "P1") (pin "2") (pinfunction "2_2") (pintype "passive"))
      (node (ref "R44") (pin "1") (pinfunction "1_1") (pintype "passive"))
    )
    (net (code "12") (name "/QSPI_CS") (class "Default")
      (node (ref "IC17") (pin "10") (pinfunction "Z_10") (pintype "bidirectional"))
      (node (ref "IC6") (pin "1") (pinfunction "~{CS}_1") (pintype "input"))
      (node (ref "R45") (pin "2") (pinfunction "2_2") (pintype "passive"))
    )
    (net (code "13") (name "/QSPI_DQ0") (class "Default")
      (node (ref "IC17") (pin "3") (pinfunction "Z_3") (pintype "bidirectional"))
      (node (ref "IC6") (pin "5") (pinfunction "SI/SIO0_5") (pintype "bidirectional"))
    )
    (net (code "14") (name "/QSPI_DQ1") (class "Default")
      (node (ref "IC17") (pin "9") (pinfunction "Z_9") (pintype "bidirectional"))
      (node (ref "IC6") (pin "2") (pinfunction "SO/SIO1_2") (pintype "bidirectional"))
    )
    (net (code "15") (name "/QSPI_DQ2") (class "Default")
      (node (ref "IC6") (pin "3") (pinfunction "~{WP}/SIO2_3") (pintype "bidirectional"))
      (node (ref "R46") (pin "2") (pinfunction "2_2") (pintype "passive"))
    )
    (net (code "16") (name "/QSPI_DQ3") (class "Default")
      (node (ref "IC6") (pin "7") (pinfunction "~{RESET}/SIO3_7") (pintype "bidirectional"))
      (node (ref "R47") (pin "2") (pinfunction "2_2") (pintype "passive"))
    )
    (net (code "17") (name "/SC_MISO") (class "Default")
      (node (ref "IC17") (pin "8") (pinfunction "Y_8") (pintype "bidirectional"))
      (node (ref "P1") (pin "5") (pinfunction "5_5") (pintype "passive"))
    )
    (net (code "18") (name "/SC_MOSI") (class "Default")
      (node (ref "IC17") (pin "4") (pinfunction "Y_4") (pintype "bidirectional"))
      (node (ref "P1") (pin "3") (pinfunction "3_3") (pintype "passive"))
    )
    (net (code "19") (name "/SC_SCLK") (class "Default")
      (node (ref "IC17") (pin "1") (pinfunction "Y_1") (pintype "bidirectional"))
      (node (ref "P1") (pin "1") (pinfunction "1_1") (pintype "passive"))
    )
    (net (code "20") (name "/SC_SSEL") (class "Default")
      (node (ref "IC17") (pin "11") (pinfunction "Y_11") (pintype "bidirectional"))
      (node (ref "P1") (pin "7") (pinfunction "7_7") (pintype "passive"))
    )
    (net (code "22") (name "GND") (class "Default")
      (node (ref "C100") (pin "1") (pinfunction "1_1") (pintype "passive"))
      (node (ref "C101") (pin "1") (pinfunction "1_1") (pintype "passive"))
      (node (ref "C102") (pin "1") (pinfunction "1_1") (pintype "passive"))
      (node (ref "C103") (pin "2") (pinfunction "2_2") (pintype "passive"))
      (node (ref "C104") (pin "2") (pinfunction "2_2") (pintype "passive"))
      (node (ref "C105") (pin "1") (pinfunction "1_1") (pintype "passive"))
      (node (ref "C106") (pin "1") (pinfunction "1_1") (pintype "passive"))
      (node (ref "C107") (pin "1") (pinfunction "1_1") (pintype "passive"))
      (node (ref "C108") (pin "1") (pinfunction "1_1") (pintype "passive"))
      (node (ref "C109") (pin "1") (pinfunction "1_1") (pintype "passive"))
      (node (ref "C110") (pin "1") (pinfunction "1_1") (pintype "passive"))
      (node (ref "C111") (pin "1") (pinfunction "1_1") (pintype "passive"))
      (node (ref "C112") (pin "1") (pinfunction "1_1") (pintype "passive"))
      (node (ref "C113") (pin "1") (pinfunction "1_1") (pintype "passive"))
      (node (ref "C114") (pin "1") (pinfunction "1_1") (pintype "passive"))
      (node (ref "C115") (pin "1") (pinfunction "1_1") (pintype "passive"))
      (node (ref "C116") (pin "1") (pinfunction "1_1") (pintype "passive"))
      (node (ref "C117") (pin "1") (pinfunction "1_1") (pintype "passive"))
      (node (ref "C118") (pin "1") (pinfunction "1_1") (pintype "passive"))
      (node (ref "C119") (pin "1") (pinfunction "1_1") (pintype "passive"))
      (node (ref "C120") (pin "1") (pinfunction "1_1") (pintype "passive"))
      (node (ref "C121") (pin "1") (pinfunction "1_1") (pintype "passive"))
      (node (ref "C122") (pin "1") (pinfunction "1_1") (pintype "passive"))
      (node (ref "C123") (pin "1") (pinfunction "1_1") (pintype "passive"))
      (node (ref "C124") (pin "1") (pinfunction "1_1") (pintype "passive"))
      (node (ref "C125") (pin "1") (pinfunction "1_1") (pintype "passive"))
      (node (ref "C126") (pin "1") (pinfunction "1_1") (pintype "passive"))
      (node (ref "C127") (pin "1") (pinfunction "1_1") (pintype "passive"))
      (node (ref "C128") (pin "1") (pinfunction "1_1") (pintype "passive"))
      (node (ref "C129") (pin "1") (pinfunction "1_1") (pintype "passive"))
      (node (ref "C130") (pin "1") (pinfunction "1_1") (pintype "passive"))
      (node (ref "C131") (pin "1") (pinfunction "1_1") (pintype "passive"))
      (node (ref "C132") (pin "1") (pinfunction "1_1") (pintype "passive"))
      (node (ref "C133") (pin "1") (pinfunction "1_1") (pintype "passive"))
      (node (ref "C134") (pin "1") (pinfunction "1_1") (pintype "passive"))
      (node (ref "C332") (pin "2") (pinfunction "2_2") (pintype "passive"))
      (node (ref "C56") (pin "1") (pinfunction "1_1") (pintype "passive"))
      (node (ref "C57") (pin "1") (pinfunction "1_1") (pintype "passive"))
      (node (ref "C58") (pin "1") (pinfunction "1_1") (pintype "passive"))
      (node (ref "C59") (pin "1") (pinfunction "1_1") (pintype "passive"))
      (node (ref "C60") (pin "1") (pinfunction "1_1") (pintype "passive"))
      (node (ref "C61") (pin "1") (pinfunction "1_1") (pintype "passive"))
      (node (ref "C62") (pin "1") (pinfunction "1_1") (pintype "passive"))
      (node (ref "C63") (pin "1") (pinfunction "1_1") (pintype "passive"))
      (node (ref "C64") (pin "1") (pinfunction "1_1") (pintype "passive"))
      (node (ref "C65") (pin "1") (pinfunction "1_1") (pintype "passive"))
      (node (ref "C66") (pin "1") (pinfunction "1_1") (pintype "passive"))
      (node (ref "C67") (pin "1") (pinfunction "1_1") (pintype "passive"))
      (node (ref "C68") (pin "1") (pinfunction "1_1") (pintype "passive"))
      (node (ref "C69") (pin "1") (pinfunction "1_1") (pintype "passive"))
      (node (ref "C70") (pin "1") (pinfunction "1_1") (pintype "passive"))
      (node (ref "C71") (pin "1") (pinfunction "1_1") (pintype "passive"))
      (node (ref "C72") (pin "1") (pinfunction "1_1") (pintype "passive"))
      (node (ref "C73") (pin "1") (pinfunction "1_1") (pintype "passive"))
      (node (ref "C74") (pin "1") (pinfunction "1_1") (pintype "passive"))
      (node (ref "C75") (pin "1") (pinfunction "1_1") (pintype "passive"))
      (node (ref "C76") (pin "1") (pinfunction "1_1") (pintype "passive"))
      (node (ref "C77") (pin "1") (pinfunction "1_1") (pintype "passive"))
      (node (ref "C78") (pin "1") (pinfunction "1_1") (pintype "passive"))
      (node (ref "C79") (pin "1") (pinfunction "1_1") (pintype "passive"))
      (node (ref "C80") (pin "1") (pinfunction "1_1") (pintype "passive"))
      (node (ref "C81") (pin "1") (pinfunction "1_1") (pintype "passive"))
      (node (ref "C82") (pin "1") (pinfunction "1_1") (pintype "passive"))
      (node (ref "C83") (pin "1") (pinfunction "1_1") (pintype "passive"))
      (node (ref "C84") (pin "1") (pinfunction "1_1") (pintype "passive"))
      (node (ref "C85") (pin "1") (pinfunction "1_1") (pintype "passive"))
      (node (ref "C86") (pin "1") (pinfunction "1_1") (pintype "passive"))
      (node (ref "C87") (pin "1") (pinfunction "1_1") (pintype "passive"))
      (node (ref "C88") (pin "1") (pinfunction "1_1") (pintype "passive"))
      (node (ref "C89") (pin "1") (pinfunction "1_1") (pintype "passive"))
      (node (ref "C90") (pin "1") (pinfunction "1_1") (pintype "passive"))
      (node (ref "C91") (pin "1") (pinfunction "1_1") (pintype "passive"))
      (node (ref "C92") (pin "1") (pinfunction "1_1") (pintype "passive"))
      (node (ref "C93") (pin "1") (pinfunction "1_1") (pintype "passive"))
      (node (ref "C94") (pin "1") (pinfunction "1_1") (pintype "passive"))
      (node (ref "C95") (pin "1") (pinfunction "1_1") (pintype "passive"))
      (node (ref "C96") (pin "1") (pinfunction "1_1") (pintype "passive"))
      (node (ref "C97") (pin "1") (pinfunction "1_1") (pintype "passive"))
      (node (ref "C98") (pin "1") (pinfunction "1_1") (pintype "passive"))
      (node (ref "C99") (pin "1") (pinfunction "1_1") (pintype "passive"))
      (node (ref "D2") (pin "1") (pinfunction "GND_1") (pintype "power_in"))
      (node (ref "D3") (pin "1") (pinfunction "GND_1") (pintype "power_in"))
      (node (ref "IC17") (pin "7") (pinfunction "GND_7") (pintype "power_in"))
      (node (ref "IC4") (pin "A1") (pinfunction "GND_A1") (pintype "power_in"))
      (node (ref "IC4") (pin "A11") (pinfunction "GND_A11") (pintype "power_in"))
      (node (ref "IC4") (pin "A18") (pinfunction "GND_A18") (pintype "power_in"))
      (node (ref "IC4") (pin "A5") (pinfunction "GND_A5") (pintype "power_in"))
      (node (ref "IC4") (pin "A7") (pinfunction "GND_A7") (pintype "power_in"))
      (node (ref "IC4") (pin "A8") (pinfunction "GND_A8") (pintype "power_in"))
      (node (ref "IC4") (pin "B18") (pinfunction "GND_B18") (pintype "power_in"))
      (node (ref "IC4") (pin "B3") (pinfunction "GND_B3") (pintype "power_in"))
      (node (ref "IC4") (pin "B7") (pinfunction "GND_B7") (pintype "power_in"))
      (node (ref "IC4") (pin "B8") (pinfunction "GND_B8") (pintype "power_in"))
      (node (ref "IC4") (pin "C15") (pinfunction "GND_C15") (pintype "power_in"))
      (node (ref "IC4") (pin "C2") (pinfunction "GND_C2") (pintype "power_in"))
      (node (ref "IC4") (pin "C6") (pinfunction "GND_C6") (pintype "power_in"))
      (node (ref "IC4") (pin "C7") (pinfunction "GND_C7") (pintype "power_in"))
      (node (ref "IC4") (pin "D12") (pinfunction "GND_D12") (pintype "power_in"))
      (node (ref "IC4") (pin "D3") (pinfunction "GND_D3") (pintype "power_in"))
      (node (ref "IC4") (pin "D4") (pinfunction "GND_D4") (pintype "power_in"))
      (node (ref "IC4") (pin "D7") (pinfunction "GND_D7") (pintype "power_in"))
      (node (ref "IC4") (pin "E2") (pinfunction "GND_E2") (pintype "power_in"))
      (node (ref "IC4") (pin "E6") (pinfunction "GND_E6") (pintype "power_in"))
      (node (ref "IC4") (pin "E7") (pinfunction "GND_E7") (pintype "power_in"))
      (node (ref "IC4") (pin "E9") (pinfunction "GND_E9") (pintype "power_in"))
      (node (ref "IC4") (pin "F10") (pinfunction "GND_F10") (pintype "power_in"))
      (node (ref "IC4") (pin "F13") (pinfunction "M2_0_F13") (pintype "input"))
      (node (ref "IC4") (pin "F16") (pinfunction "GND_F16") (pintype "power_in"))
      (node (ref "IC4") (pin "F4") (pinfunction "GND_F4") (pintype "power_in"))
      (node (ref "IC4") (pin "F6") (pinfunction "GND_F6") (pintype "power_in"))
      (node (ref "IC4") (pin "G1") (pinfunction "GND_G1") (pintype "power_in"))
      (node (ref "IC4") (pin "G11") (pinfunction "GND_G11") (pintype "power_in"))
      (node (ref "IC4") (pin "G13") (pinfunction "GND_G13") (pintype "power_in"))
      (node (ref "IC4") (pin "G5") (pinfunction "GND_G5") (pintype "power_in"))
      (node (ref "IC4") (pin "G6") (pinfunction "GND_G6") (pintype "power_in"))
      (node (ref "IC4") (pin "G7") (pinfunction "GND_G7") (pintype "power_in"))
      (node (ref "IC4") (pin "G9") (pinfunction "GND_G9") (pintype "power_in"))
      (node (ref "IC4") (pin "H10") (pinfunction "GND_H10") (pintype "power_in"))
      (node (ref "IC4") (pin "H12") (pinfunction "GND_H12") (pintype "power_in"))
      (node (ref "IC4") (pin "H3") (pinfunction "GND_H3") (pintype "power_in"))
      (node (ref "IC4") (pin "H4") (pinfunction "GND_H4") (pintype "power_in"))
      (node (ref "IC4") (pin "H5") (pinfunction "GND_H5") (pintype "power_in"))
      (node (ref "IC4") (pin "H6") (pinfunction "GND_H6") (pintype "power_in"))
      (node (ref "IC4") (pin "H8") (pinfunction "GND_H8") (pintype "power_in"))
      (node (ref "IC4") (pin "J1") (pinfunction "GND_J1") (pintype "power_in"))
      (node (ref "IC4") (pin "J11") (pinfunction "GND_J11") (pintype "power_in"))
      (node (ref "IC4") (pin "J13") (pinfunction "GND_J13") (pintype "power_in"))
      (node (ref "IC4") (pin "J17") (pinfunction "GND_J17") (pintype "power_in"))
      (node (ref "IC4") (pin "J2") (pinfunction "GND_J2") (pintype "power_in"))
      (node (ref "IC4") (pin "J3") (pinfunction "GND_J3") (pintype "power_in"))
      (node (ref "IC4") (pin "J7") (pinfunction "GND_J7") (pintype "power_in"))
      (node (ref "IC4") (pin "K12") (pinfunction "GND_K12") (pintype "power_in"))
      (node (ref "IC4") (pin "K14") (pinfunction "GND_K14") (pintype "power_in"))
      (node (ref "IC4") (pin "K4") (pinfunction "GND_K4") (pintype "power_in"))
      (node (ref "IC4") (pin "K8") (pinfunction "GND_K8") (pintype "power_in"))
      (node (ref "IC4") (pin "K9") (pinfunction "VREFN_0_K9") (pintype "input"))
      (node (ref "IC4") (pin "L1") (pinfunction "GND_L1") (pintype "power_in"))
      (node (ref "IC4") (pin "L10") (pinfunction "VREFP_0_L10") (pintype "input"))
      (node (ref "IC4") (pin "L11") (pinfunction "GND_L11") (pintype "power_in"))
      (node (ref "IC4") (pin "L13") (pinfunction "GND_L13") (pintype "power_in"))
      (node (ref "IC4") (pin "L7") (pinfunction "GND_L7") (pintype "power_in"))
      (node (ref "IC4") (pin "L9") (pinfunction "VN_0_L9") (pintype "input"))
      (node (ref "IC4") (pin "M10") (pinfunction "DXP_0_M10") (pintype "input"))
      (node (ref "IC4") (pin "M12") (pinfunction "GND_M12") (pintype "power_in"))
      (node (ref "IC4") (pin "M18") (pinfunction "GND_M18") (pintype "power_in"))
      (node (ref "IC4") (pin "M8") (pinfunction "GND_M8") (pintype "power_in"))
      (node (ref "IC4") (pin "M9") (pinfunction "DXN_0_M9") (pintype "input"))
      (node (ref "IC4") (pin "N11") (pinfunction "GND_N11") (pintype "power_in"))
      (node (ref "IC4") (pin "N13") (pinfunction "GND_N13") (pintype "power_in"))
      (node (ref "IC4") (pin "N15") (pinfunction "GND_N15") (pintype "power_in"))
      (node (ref "IC4") (pin "N5") (pinfunction "GND_N5") (pintype "power_in"))
      (node (ref "IC4") (pin "N7") (pinfunction "GND_N7") (pintype "power_in"))
      (node (ref "IC4") (pin "N9") (pinfunction "GND_N9") (pintype "power_in"))
      (node (ref "IC4") (pin "P12") (pinfunction "GND_P12") (pintype "power_in"))
      (node (ref "IC4") (pin "P2") (pinfunction "GND_P2") (pintype "power_in"))
      (node (ref "IC4") (pin "P8") (pinfunction "GND_P8") (pintype "power_in"))
      (node (ref "IC4") (pin "R11") (pinfunction "M1_0_R11") (pintype "input"))
      (node (ref "IC4") (pin "R9") (pinfunction "GND_R9") (pintype "power_in"))
      (node (ref "IC4") (pin "T16") (pinfunction "GND_T16") (pintype "power_in"))
      (node (ref "IC4") (pin "T6") (pinfunction "GND_T6") (pintype "power_in"))
      (node (ref "IC4") (pin "U13") (pinfunction "GND_U13") (pintype "power_in"))
      (node (ref "IC4") (pin "U3") (pinfunction "GND_U3") (pintype "power_in"))
      (node (ref "IC4") (pin "V1") (pinfunction "GND_V1") (pintype "power_in"))
      (node (ref "IC4") (pin "V10") (pinfunction "GND_V10") (pintype "power_in"))
      (node (ref "IC4") (pin "V18") (pinfunction "GND_V18") (pintype "power_in"))
      (node (ref "IC5") (pin "3") (pinfunction "VSS_3") (pintype "power_in"))
      (node (ref "IC6") (pin "4") (pinfunction "GND_4") (pintype "power_in"))
      (node (ref "IC6") (pin "9") (pinfunction "EP_9") (pintype "power_in"))
      (node (ref "J6") (pin "1") (pinfunction "1_1") (pintype "bidirectional"))
      (node (ref "J6") (pin "11") (pinfunction "11_11") (pintype "bidirectional"))
      (node (ref "J6") (pin "3") (pinfunction "3_3") (pintype "bidirectional"))
      (node (ref "J6") (pin "5") (pinfunction "5_5") (pintype "bidirectional"))
      (node (ref "J6") (pin "7") (pinfunction "7_7") (pintype "bidirectional"))
      (node (ref "J6") (pin "9") (pinfunction "9_9") (pintype "bidirectional"))
      (node (ref "L1") (pin "2") (pinfunction "2_2") (pintype "passive"))
      (node (ref "P1") (pin "8") (pinfunction "8_8") (pintype "passive"))
      (node (ref "R147") (pin "2") (pinfunction "2_2") (pintype "passive"))
      (node (ref "R54") (pin "1") (pinfunction "1_1") (pintype "passive"))
      (node (ref "T6") (pin "2") (pinfunction "S_2") (pintype "passive"))
    )
    (net (code "23") (name "MGTAVCC") (class "Default")
      (node (ref "C56") (pin "2") (pinfunction "2_2") (pintype "passive"))
      (node (ref "C57") (pin "2") (pinfunction "2_2") (pintype "passive"))
      (node (ref "C58") (pin "2") (pinfunction "2_2") (pintype "passive"))
      (node (ref "C59") (pin "2") (pinfunction "2_2") (pintype "passive"))
      (node (ref "C60") (pin "2") (pinfunction "2_2") (pintype "passive"))
      (node (ref "C61") (pin "2") (pinfunction "2_2") (pintype "passive"))
      (node (ref "IC4") (pin "B4") (pinfunction "MGTAVCC_B4") (pintype "power_in"))
      (node (ref "IC4") (pin "C5") (pinfunction "MGTAVCC_C5") (pintype "power_in"))
      (node (ref "IC4") (pin "E5") (pinfunction "MGTAVCC_E5") (pintype "power_in"))
      (node (ref "IC4") (pin "F5") (pinfunction "MGTAVCC_F5") (pintype "power_in"))
    )
    (net (code "24") (name "MGTAVTT") (class "Default")
      (node (ref "C62") (pin "2") (pinfunction "2_2") (pintype "passive"))
      (node (ref "C63") (pin "2") (pinfunction "2_2") (pintype "passive"))
      (node (ref "C64") (pin "2") (pinfunction "2_2") (pintype "passive"))
      (node (ref "C65") (pin "2") (pinfunction "2_2") (pintype "passive"))
      (node (ref "C66") (pin "2") (pinfunction "2_2") (pintype "passive"))
      (node (ref "C67") (pin "2") (pinfunction "2_2") (pintype "passive"))
      (node (ref "IC4") (pin "A2") (pinfunction "MGTAVTT_A2") (pintype "power_in"))
      (node (ref "IC4") (pin "C1") (pinfunction "MGTAVTT_C1") (pintype "power_in"))
      (node (ref "IC4") (pin "E1") (pinfunction "MGTAVTT_E1") (pintype "power_in"))
      (node (ref "IC4") (pin "F3") (pinfunction "MGTAVTT_F3") (pintype "power_in"))
      (node (ref "IC4") (pin "G2") (pinfunction "MGTAVTT_G2") (pintype "power_in"))
    )
    (net (code "25") (name "Net-(IC4D-PROGRAM_B_0)") (class "Default")
      (node (ref "IC4") (pin "P10") (pinfunction "PROGRAM_B_0_P10") (pintype "input"))
      (node (ref "R43") (pin "1") (pinfunction "1_1") (pintype "passive"))
    )
    (net (code "26") (name "Net-(IC4D-VP_0)") (class "Default")
      (node (ref "IC4") (pin "K10") (pinfunction "VP_0_K10") (pintype "input"))
      (node (ref "R147") (pin "1") (pinfunction "1_1") (pintype "passive"))
    )
    (net (code "27") (name "Net-(IC4I-GNDADC_0)") (class "Default")
      (node (ref "IC4") (pin "J9") (pinfunction "GNDADC_0_J9") (pintype "power_in"))
      (node (ref "L1") (pin "1") (pinfunction "1_1") (pintype "passive"))
    )
    (net (code "28") (name "Net-(IC5-~{RST})") (class "Default")
      (node (ref "IC5") (pin "1") (pinfunction "~{RST}_1") (pintype "open_collector"))
      (node (ref "R170") (pin "1") (pinfunction "1_1") (pintype "passive"))
      (node (ref "R44") (pin "2") (pinfunction "2_2") (pintype "passive"))
    )
    (net (code "29") (name "Net-(LD8-A)") (class "Default")
      (node (ref "LD8") (pin "2") (pinfunction "A_2") (pintype "passive"))
      (node (ref "R48") (pin "1") (pinfunction "1_1") (pintype "passive"))
    )
    (net (code "30") (name "Net-(LD8-C)") (class "Default")
      (node (ref "LD8") (pin "1") (pinfunction "C_1") (pintype "passive"))
      (node (ref "T6") (pin "3") (pinfunction "D_3") (pintype "passive"))
    )
    (net (code "31") (name "P1V0") (class "Default")
      (node (ref "C103") (pin "1") (pinfunction "1_1") (pintype "passive"))
      (node (ref "C104") (pin "1") (pinfunction "1_1") (pintype "passive"))
      (node (ref "C107") (pin "2") (pinfunction "2_2") (pintype "passive"))
      (node (ref "C108") (pin "2") (pinfunction "2_2") (pintype "passive"))
      (node (ref "C109") (pin "2") (pinfunction "2_2") (pintype "passive"))
      (node (ref "C110") (pin "2") (pinfunction "2_2") (pintype "passive"))
      (node (ref "C111") (pin "2") (pinfunction "2_2") (pintype "passive"))
      (node (ref "C112") (pin "2") (pinfunction "2_2") (pintype "passive"))
      (node (ref "C120") (pin "2") (pinfunction "2_2") (pintype "passive"))
      (node (ref "C121") (pin "2") (pinfunction "2_2") (pintype "passive"))
      (node (ref "C122") (pin "2") (pinfunction "2_2") (pintype "passive"))
      (node (ref "C123") (pin "2") (pinfunction "2_2") (pintype "passive"))
      (node (ref "C124") (pin "2") (pinfunction "2_2") (pintype "passive"))
      (node (ref "C125") (pin "2") (pinfunction "2_2") (pintype "passive"))
      (node (ref "C126") (pin "2") (pinfunction "2_2") (pintype "passive"))
      (node (ref "C127") (pin "2") (pinfunction "2_2") (pintype "passive"))
      (node (ref "C128") (pin "2") (pinfunction "2_2") (pintype "passive"))
      (node (ref "C129") (pin "2") (pinfunction "2_2") (pintype "passive"))
      (node (ref "C130") (pin "2") (pinfunction "2_2") (pintype "passive"))
      (node (ref "C131") (pin "2") (pinfunction "2_2") (pintype "passive"))
      (node (ref "IC4") (pin "F11") (pinfunction "VCCBRAM_F11") (pintype "power_in"))
      (node (ref "IC4") (pin "F7") (pinfunction "VCCINT_F7") (pintype "power_in"))
      (node (ref "IC4") (pin "F9") (pinfunction "VCCINT_F9") (pintype "power_in"))
      (node (ref "IC4") (pin "G10") (pinfunction "VCCBRAM_G10") (pintype "power_in"))
      (node (ref "IC4") (pin "G8") (pinfunction "VCCINT_G8") (pintype "power_in"))
      (node (ref "IC4") (pin "H11") (pinfunction "VCCBRAM_H11") (pintype "power_in"))
      (node (ref "IC4") (pin "H7") (pinfunction "VCCINT_H7") (pintype "power_in"))
      (node (ref "IC4") (pin "H9") (pinfunction "VCCINT_H9") (pintype "power_in"))
      (node (ref "IC4") (pin "J12") (pinfunction "VCCINT_J12") (pintype "power_in"))
      (node (ref "IC4") (pin "J8") (pinfunction "VCCINT_J8") (pintype "power_in"))
      (node (ref "IC4") (pin "K11") (pinfunction "VCCINT_K11") (pintype "power_in"))
      (node (ref "IC4") (pin "K7") (pinfunction "VCCINT_K7") (pintype "power_in"))
      (node (ref "IC4") (pin "L12") (pinfunction "VCCINT_L12") (pintype "power_in"))
      (node (ref "IC4") (pin "L8") (pinfunction "VCCINT_L8") (pintype "power_in"))
      (node (ref "IC4") (pin "M11") (pinfunction "VCCINT_M11") (pintype "power_in"))
      (node (ref "IC4") (pin "M7") (pinfunction "VCCINT_M7") (pintype "power_in"))
      (node (ref "IC4") (pin "N10") (pinfunction "VCCINT_N10") (pintype "power_in"))
      (node (ref "IC4") (pin "N12") (pinfunction "VCCINT_N12") (pintype "power_in"))
      (node (ref "IC4") (pin "N8") (pinfunction "VCCINT_N8") (pintype "power_in"))
      (node (ref "IC4") (pin "P11") (pinfunction "VCCINT_P11") (pintype "power_in"))
      (node (ref "IC4") (pin "P9") (pinfunction "VCCINT_P9") (pintype "power_in"))
    )
    (net (code "32") (name "P1V8") (class "Default")
      (node (ref "C113") (pin "2") (pinfunction "2_2") (pintype "passive"))
      (node (ref "C114") (pin "2") (pinfunction "2_2") (pintype "passive"))
      (node (ref "C115") (pin "2") (pinfunction "2_2") (pintype "passive"))
      (node (ref "C116") (pin "2") (pinfunction "2_2") (pintype "passive"))
      (node (ref "C117") (pin "2") (pinfunction "2_2") (pintype "passive"))
      (node (ref "C118") (pin "2") (pinfunction "2_2") (pintype "passive"))
      (node (ref "C119") (pin "2") (pinfunction "2_2") (pintype "passive"))
      (node (ref "IC4") (pin "E11") (pinfunction "VCCBATT_0_E11") (pintype "power_in"))
      (node (ref "IC4") (pin "G12") (pinfunction "VCCAUX_G12") (pintype "power_in"))
      (node (ref "IC4") (pin "H13") (pinfunction "VCCAUX_H13") (pintype "power_in"))
      (node (ref "IC4") (pin "K13") (pinfunction "VCCAUX_K13") (pintype "power_in"))
      (node (ref "IC4") (pin "M13") (pinfunction "VCCAUX_M13") (pintype "power_in"))
      (node (ref "IC4") (pin "P13") (pinfunction "VCCAUX_P13") (pintype "power_in"))
      (node (ref "L2") (pin "2") (pinfunction "2_2") (pintype "passive"))
    )
    (net (code "33") (name "P2V5") (class "Default")
      (node (ref "C71") (pin "2") (pinfunction "2_2") (pintype "passive"))
      (node (ref "C72") (pin "2") (pinfunction "2_2") (pintype "passive"))
      (node (ref "C73") (pin "2") (pinfunction "2_2") (pintype "passive"))
      (node (ref "C74") (pin "2") (pinfunction "2_2") (pintype "passive"))
      (node (ref "C75") (pin "2") (pinfunction "2_2") (pintype "passive"))
      (node (ref "C76") (pin "2") (pinfunction "2_2") (pintype "passive"))
      (node (ref "C77") (pin "2") (pinfunction "2_2") (pintype "passive"))
      (node (ref "C78") (pin "2") (pinfunction "2_2") (pintype "passive"))
      (node (ref "C79") (pin "2") (pinfunction "2_2") (pintype "passive"))
      (node (ref "C80") (pin "2") (pinfunction "2_2") (pintype "passive"))
      (node (ref "C81") (pin "2") (pinfunction "2_2") (pintype "passive"))
      (node (ref "C82") (pin "2") (pinfunction "2_2") (pintype "passive"))
      (node (ref "C83") (pin "2") (pinfunction "2_2") (pintype "passive"))
      (node (ref "IC4") (pin "A16") (pinfunction "VCCO_15_A16") (pintype "power_in"))
      (node (ref "IC4") (pin "B13") (pinfunction "VCCO_15_B13") (pintype "power_in"))
      (node (ref "IC4") (pin "C10") (pinfunction "VCCO_15_C10") (pintype "power_in"))
      (node (ref "IC4") (pin "D17") (pinfunction "VCCO_15_D17") (pintype "power_in"))
      (node (ref "IC4") (pin "E14") (pinfunction "VCCO_15_E14") (pintype "power_in"))
      (node (ref "IC4") (pin "G18") (pinfunction "VCCO_15_G18") (pintype "power_in"))
      (node (ref "IC4") (pin "H15") (pinfunction "VCCO_15_H15") (pintype "power_in"))
    )
    (net (code "34") (name "P3V3") (class "Default")
      (node (ref "C100") (pin "2") (pinfunction "2_2") (pintype "passive"))
      (node (ref "C101") (pin "2") (pinfunction "2_2") (pintype "passive"))
      (node (ref "C102") (pin "2") (pinfunction "2_2") (pintype "passive"))
      (node (ref "C132") (pin "2") (pinfunction "2_2") (pintype "passive"))
      (node (ref "C68") (pin "2") (pinfunction "2_2") (pintype "passive"))
      (node (ref "C69") (pin "2") (pinfunction "2_2") (pintype "passive"))
      (node (ref "C70") (pin "2") (pinfunction "2_2") (pintype "passive"))
      (node (ref "C84") (pin "2") (pinfunction "2_2") (pintype "passive"))
      (node (ref "C85") (pin "2") (pinfunction "2_2") (pintype "passive"))
      (node (ref "C86") (pin "2") (pinfunction "2_2") (pintype "passive"))
      (node (ref "C87") (pin "2") (pinfunction "2_2") (pintype "passive"))
      (node (ref "C88") (pin "2") (pinfunction "2_2") (pintype "passive"))
      (node (ref "C89") (pin "2") (pinfunction "2_2") (pintype "passive"))
      (node (ref "C90") (pin "2") (pinfunction "2_2") (pintype "passive"))
      (node (ref "C91") (pin "2") (pinfunction "2_2") (pintype "passive"))
      (node (ref "C92") (pin "2") (pinfunction "2_2") (pintype "passive"))
      (node (ref "C93") (pin "2") (pinfunction "2_2") (pintype "passive"))
      (node (ref "C94") (pin "2") (pinfunction "2_2") (pintype "passive"))
      (node (ref "C95") (pin "2") (pinfunction "2_2") (pintype "passive"))
      (node (ref "C96") (pin "2") (pinfunction "2_2") (pintype "passive"))
      (node (ref "C97") (pin "2") (pinfunction "2_2") (pintype "passive"))
      (node (ref "C98") (pin "2") (pinfunction "2_2") (pintype "passive"))
      (node (ref "C99") (pin "2") (pinfunction "2_2") (pintype "passive"))
      (node (ref "D2") (pin "4") (pinfunction "VCC_4") (pintype "power_in"))
      (node (ref "D3") (pin "4") (pinfunction "VCC_4") (pintype "power_in"))
      (node (ref "FB1") (pin "1") (pinfunction "1_1") (pintype "passive"))
      (node (ref "IC4") (pin "E10") (pinfunction "VCCO_0_E10") (pintype "power_in"))
      (node (ref "IC4") (pin "E12") (pinfunction "CFGBVS_0_E12") (pintype "input"))
      (node (ref "IC4") (pin "L16") (pinfunction "VCCO_14_L16") (pintype "power_in"))
      (node (ref "IC4") (pin "L6") (pinfunction "VCCO_34_L6") (pintype "power_in"))
      (node (ref "IC4") (pin "M3") (pinfunction "VCCO_34_M3") (pintype "power_in"))
      (node (ref "IC4") (pin "P17") (pinfunction "VCCO_14_P17") (pintype "power_in"))
      (node (ref "IC4") (pin "P7") (pinfunction "VCCO_34_P7") (pintype "power_in"))
      (node (ref "IC4") (pin "R10") (pinfunction "VCCO_0_R10") (pintype "power_in"))
      (node (ref "IC4") (pin "R12") (pinfunction "M0_0_R12") (pintype "input"))
      (node (ref "IC4") (pin "R14") (pinfunction "VCCO_14_R14") (pintype "power_in"))
      (node (ref "IC4") (pin "R4") (pinfunction "VCCO_34_R4") (pintype "power_in"))
      (node (ref "IC4") (pin "T1") (pinfunction "VCCO_34_T1") (pintype "power_in"))
      (node (ref "IC4") (pin "T11") (pinfunction "VCCO_14_T11") (pintype "power_in"))
      (node (ref "IC4") (pin "U18") (pinfunction "VCCO_14_U18") (pintype "power_in"))
      (node (ref "IC4") (pin "U8") (pinfunction "VCCO_14_U8") (pintype "power_in"))
      (node (ref "IC4") (pin "V15") (pinfunction "VCCO_14_V15") (pintype "power_in"))
      (node (ref "IC4") (pin "V5") (pinfunction "VCCO_34_V5") (pintype "power_in"))
      (node (ref "IC5") (pin "2") (pinfunction "VDD_2") (pintype "power_in"))
      (node (ref "J6") (pin "2") (pinfunction "2_2") (pintype "bidirectional"))
      (node (ref "R170") (pin "2") (pinfunction "2_2") (pintype "passive"))
      (node (ref "R43") (pin "2") (pinfunction "2_2") (pintype "passive"))
      (node (ref "R45") (pin "1") (pinfunction "1_1") (pintype "passive"))
      (node (ref "R46") (pin "1") (pinfunction "1_1") (pintype "passive"))
      (node (ref "R47") (pin "1") (pinfunction "1_1") (pintype "passive"))
      (node (ref "R48") (pin "2") (pinfunction "2_2") (pintype "passive"))
      (node (ref "R49") (pin "2") (pinfunction "2_2") (pintype "passive"))
      (node (ref "R50") (pin "2") (pinfunction "2_2") (pintype "passive"))
    )
    (net (code "35") (name "VCCADC") (class "Default")
      (node (ref "C105") (pin "2") (pinfunction "2_2") (pintype "passive"))
      (node (ref "C106") (pin "2") (pinfunction "2_2") (pintype "passive"))
      (node (ref "IC4") (pin "J10") (pinfunction "VCCADC_0_J10") (pintype "power_in"))
      (node (ref "L2") (pin "1") (pinfunction "1_1") (pintype "passive"))
    )
    (net (code "36") (name "unconnected-(J6-Pad12)") (class "Default")
      (node (ref "J6") (pin "12") (pinfunction "12_12") (pintype "bidirectional+no_connect"))
    )
    (net (code "37") (name "unconnected-(J6-Pad14)") (class "Default")
      (node (ref "J6") (pin "14") (pinfunction "14_14") (pintype "bidirectional+no_connect"))
    )
  )
)
